# anodeBoard.net
KiCad netlist of a schematic drawn in EAGLE
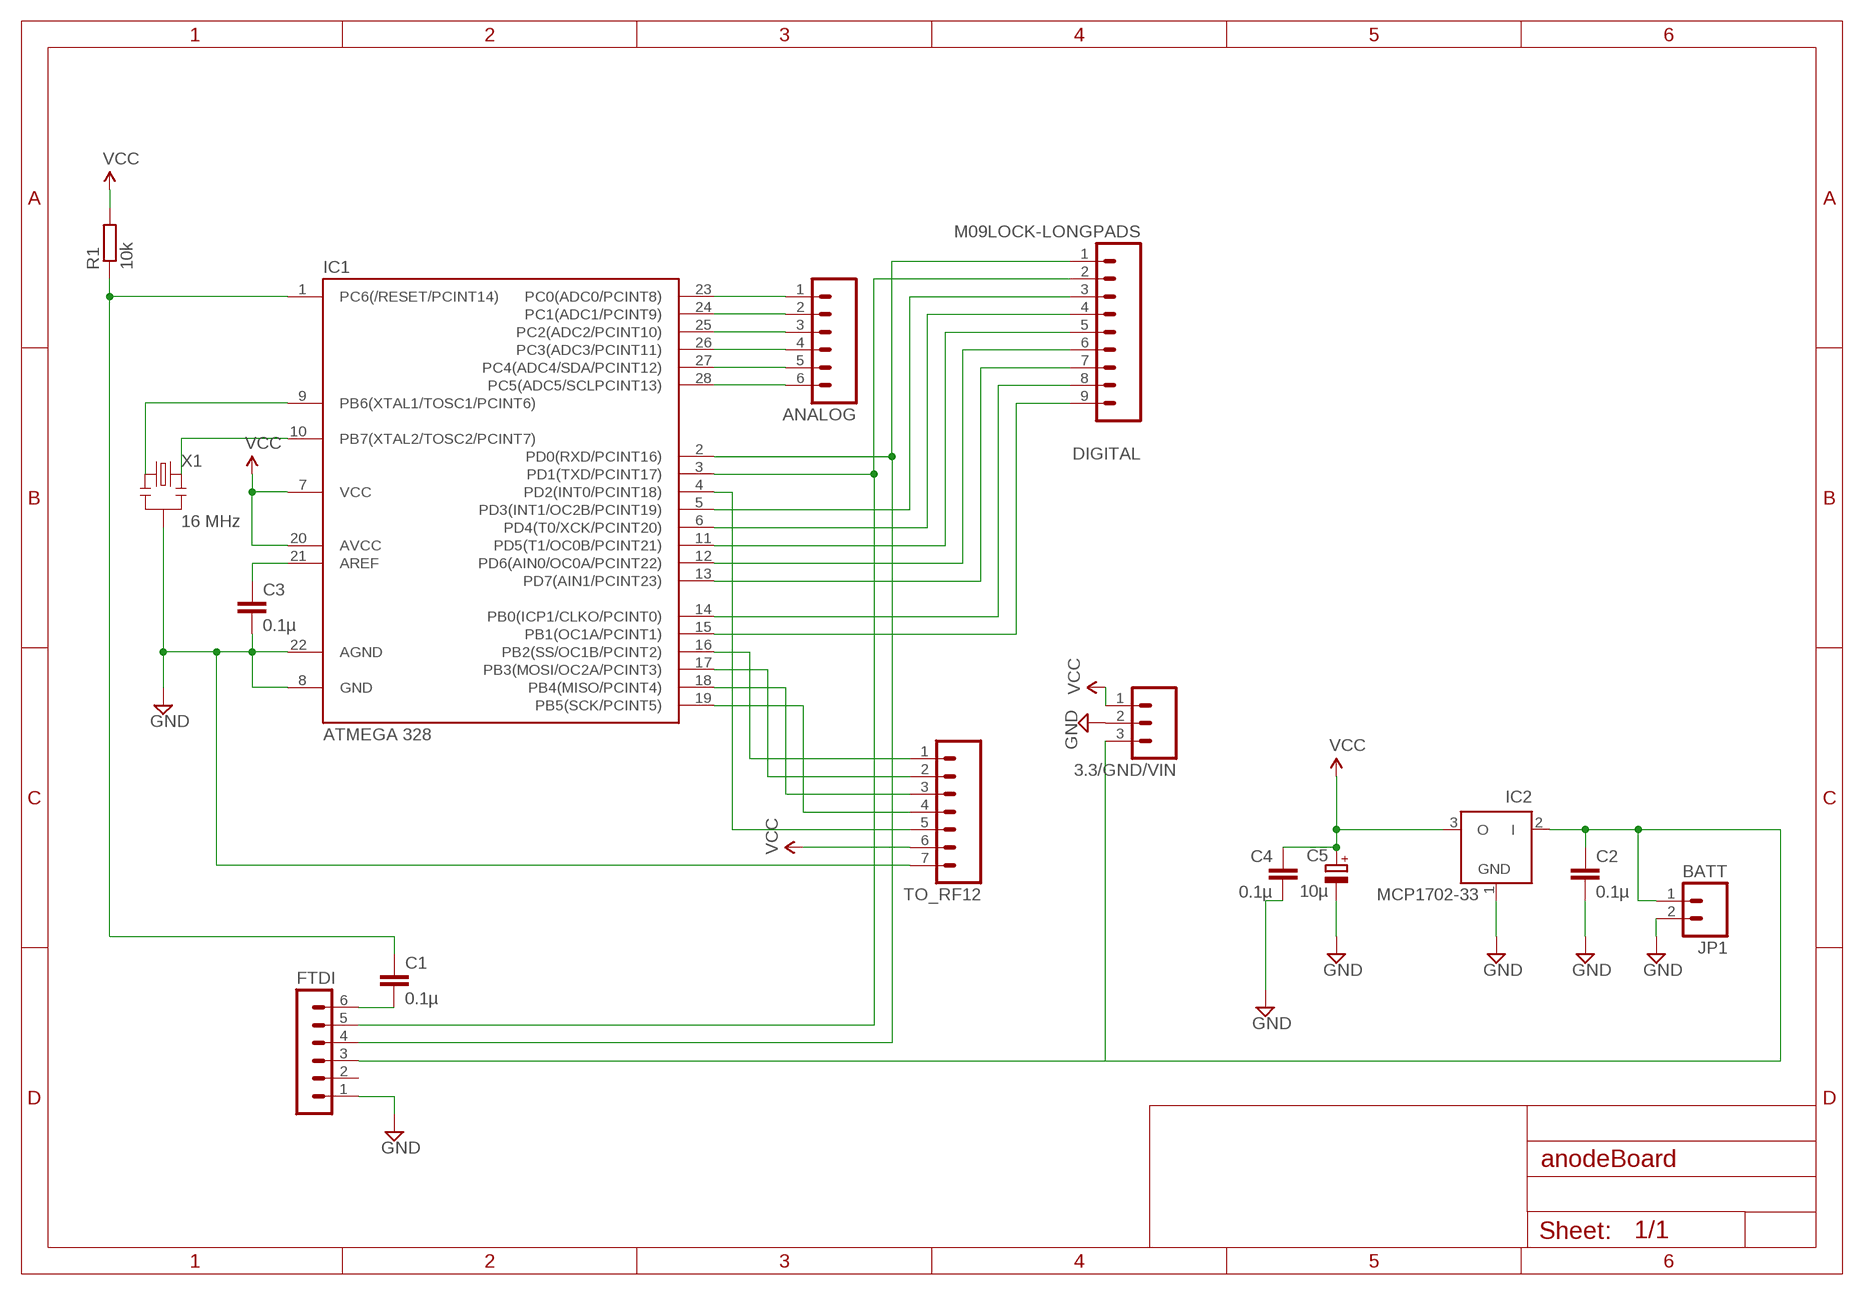
[diagram p0: schematic, sheet 1]

(export (version "E")
  (design (tool "Eeschema 10.0.6"))
  (components
    (comp (ref "3.3/GND/VIN")
      (value "M03LOCK_LONGPADS")
      (footprint "eagle-import:1X03_LOCK_LONGPADS")
      (libsource (lib "eagle-import") (part "M03LOCK_LONGPADS"))
    )
    (comp (ref "ANALOG")
      (value "M06LOCK_LONGPADS")
      (footprint "eagle-import:1X06_LOCK_LONGPADS")
      (libsource (lib "eagle-import") (part "M06LOCK_LONGPADS"))
    )
    (comp (ref "C1")
      (value "0.1µ")
      (footprint "eagle-import:C025-024X044")
      (libsource (lib "eagle-import") (part "C-EU025-024X044"))
    )
    (comp (ref "C2")
      (value "0.1µ")
      (footprint "eagle-import:C025-024X044")
      (libsource (lib "eagle-import") (part "C-EU025-024X044"))
    )
    (comp (ref "C3")
      (value "0.1µ")
      (footprint "eagle-import:C025-024X044")
      (libsource (lib "eagle-import") (part "C-EU025-024X044"))
    )
    (comp (ref "C4")
      (value "0.1µ")
      (footprint "eagle-import:C025-024X044")
      (libsource (lib "eagle-import") (part "C-EU025-024X044"))
    )
    (comp (ref "C5")
      (value "10µ")
      (footprint "eagle-import:E1,8-4")
      (libsource (lib "eagle-import") (part "CPOL-EUE1.8-4"))
    )
    (comp (ref "DIGITAL")
      (value "M09LOCK-LONGPADS")
      (footprint "eagle-import:1X09_LOCK_LONGPADS")
      (libsource (lib "eagle-import") (part "M09LOCK-LONGPADS"))
    )
    (comp (ref "FTDI")
      (value "FTDI")
      (footprint "eagle-import:MA06-1")
      (libsource (lib "eagle-import") (part "MA06-1"))
    )
    (comp (ref "IC1")
      (value "ATMEGA 328")
      (footprint "eagle-import:DIL28-3")
      (libsource (lib "eagle-import") (part "ATMEGA48/88/168-PU"))
    )
    (comp (ref "IC2")
      (value "MCP1702-33")
      (footprint "eagle-import:TO92")
      (libsource (lib "eagle-import") (part "MCP1702Z"))
    )
    (comp (ref "JP1")
      (value "BATT")
      (footprint "eagle-import:1X02_LOCK_LONGPADS")
      (libsource (lib "eagle-import") (part "M02LOCK_LONGPADS"))
    )
    (comp (ref "R1")
      (value "10k")
      (footprint "eagle-import:0204_7")
      (libsource (lib "eagle-import") (part "R-EU_0204/7"))
    )
    (comp (ref "TO_RF12")
      (value "M07LOCK_LONGPADS")
      (footprint "eagle-import:1X07_LOCK_LONGPADS")
      (libsource (lib "eagle-import") (part "M07LOCK_LONGPADS"))
    )
    (comp (ref "X1")
      (value "16 MHz")
      (footprint "eagle-import:RESONATOR-PTH")
      (libsource (lib "eagle-import") (part "RESONATORPTH"))
    )
  )
  (nets
    (net (code "1") (name "GND") (class "Default")
      (node (ref "3.3/GND/VIN") (pin "2") (pinfunction "2_2") (pintype "passive"))
      (node (ref "C2") (pin "2") (pinfunction "2_2") (pintype "passive"))
      (node (ref "C3") (pin "2") (pinfunction "2_2") (pintype "passive"))
      (node (ref "C4") (pin "2") (pinfunction "2_2") (pintype "passive"))
      (node (ref "C5") (pin "-") (pinfunction "-_-") (pintype "passive"))
      (node (ref "FTDI") (pin "1") (pinfunction "1_1") (pintype "passive"))
      (node (ref "IC1") (pin "22") (pinfunction "AGND_22") (pintype "power_in"))
      (node (ref "IC1") (pin "8") (pinfunction "GND_8") (pintype "power_in"))
      (node (ref "IC2") (pin "1") (pinfunction "GND_1") (pintype "power_in"))
      (node (ref "JP1") (pin "2") (pinfunction "2_2") (pintype "passive"))
      (node (ref "TO_RF12") (pin "7") (pinfunction "7_7") (pintype "passive"))
      (node (ref "X1") (pin "2") (pinfunction "2_2") (pintype "passive"))
    )
    (net (code "2") (name "Net-(C1-Pad2)") (class "Default")
      (node (ref "C1") (pin "2") (pinfunction "2_2") (pintype "passive"))
      (node (ref "FTDI") (pin "6") (pinfunction "6_6") (pintype "passive"))
    )
    (net (code "3") (name "Net-(IC1-AREF)") (class "Default")
      (node (ref "C3") (pin "1") (pinfunction "1_1") (pintype "passive"))
      (node (ref "IC1") (pin "21") (pinfunction "AREF_21") (pintype "passive"))
    )
    (net (code "4") (name "Net-(IC1-PB0(ICP1{slash}CLKO{slash}PCINT0))") (class "Default")
      (node (ref "DIGITAL") (pin "8") (pinfunction "8_8") (pintype "passive"))
      (node (ref "IC1") (pin "14") (pinfunction "PB0(ICP1/CLKO/PCINT0)_14") (pintype "bidirectional"))
    )
    (net (code "5") (name "Net-(IC1-PB1(OC1A{slash}PCINT1))") (class "Default")
      (node (ref "DIGITAL") (pin "9") (pinfunction "9_9") (pintype "passive"))
      (node (ref "IC1") (pin "15") (pinfunction "PB1(OC1A/PCINT1)_15") (pintype "bidirectional"))
    )
    (net (code "6") (name "Net-(IC1-PB2(SS{slash}OC1B{slash}PCINT2))") (class "Default")
      (node (ref "IC1") (pin "16") (pinfunction "PB2(SS/OC1B/PCINT2)_16") (pintype "bidirectional"))
      (node (ref "TO_RF12") (pin "1") (pinfunction "1_1") (pintype "passive"))
    )
    (net (code "7") (name "Net-(IC1-PB3(MOSI{slash}OC2A{slash}PCINT3))") (class "Default")
      (node (ref "IC1") (pin "17") (pinfunction "PB3(MOSI/OC2A/PCINT3)_17") (pintype "bidirectional"))
      (node (ref "TO_RF12") (pin "2") (pinfunction "2_2") (pintype "passive"))
    )
    (net (code "8") (name "Net-(IC1-PB4(MISO{slash}PCINT4))") (class "Default")
      (node (ref "IC1") (pin "18") (pinfunction "PB4(MISO/PCINT4)_18") (pintype "bidirectional"))
      (node (ref "TO_RF12") (pin "3") (pinfunction "3_3") (pintype "passive"))
    )
    (net (code "9") (name "Net-(IC1-PB5(SCK{slash}PCINT5))") (class "Default")
      (node (ref "IC1") (pin "19") (pinfunction "PB5(SCK/PCINT5)_19") (pintype "bidirectional"))
      (node (ref "TO_RF12") (pin "4") (pinfunction "4_4") (pintype "passive"))
    )
    (net (code "10") (name "Net-(IC1-PB6(XTAL1{slash}TOSC1{slash}PCINT6))") (class "Default")
      (node (ref "IC1") (pin "9") (pinfunction "PB6(XTAL1/TOSC1/PCINT6)_9") (pintype "bidirectional"))
      (node (ref "X1") (pin "1") (pinfunction "1_1") (pintype "passive"))
    )
    (net (code "11") (name "Net-(IC1-PB7(XTAL2{slash}TOSC2{slash}PCINT7))") (class "Default")
      (node (ref "IC1") (pin "10") (pinfunction "PB7(XTAL2/TOSC2/PCINT7)_10") (pintype "bidirectional"))
      (node (ref "X1") (pin "3") (pinfunction "3_3") (pintype "passive"))
    )
    (net (code "12") (name "Net-(IC1-PC0(ADC0{slash}PCINT8))") (class "Default")
      (node (ref "ANALOG") (pin "1") (pinfunction "1_1") (pintype "passive"))
      (node (ref "IC1") (pin "23") (pinfunction "PC0(ADC0/PCINT8)_23") (pintype "bidirectional"))
    )
    (net (code "13") (name "Net-(IC1-PC1(ADC1{slash}PCINT9))") (class "Default")
      (node (ref "ANALOG") (pin "2") (pinfunction "2_2") (pintype "passive"))
      (node (ref "IC1") (pin "24") (pinfunction "PC1(ADC1/PCINT9)_24") (pintype "bidirectional"))
    )
    (net (code "14") (name "Net-(IC1-PC2(ADC2{slash}PCINT10))") (class "Default")
      (node (ref "ANALOG") (pin "3") (pinfunction "3_3") (pintype "passive"))
      (node (ref "IC1") (pin "25") (pinfunction "PC2(ADC2/PCINT10)_25") (pintype "bidirectional"))
    )
    (net (code "15") (name "Net-(IC1-PC3(ADC3{slash}PCINT11))") (class "Default")
      (node (ref "ANALOG") (pin "4") (pinfunction "4_4") (pintype "passive"))
      (node (ref "IC1") (pin "26") (pinfunction "PC3(ADC3/PCINT11)_26") (pintype "bidirectional"))
    )
    (net (code "16") (name "Net-(IC1-PC4(ADC4{slash}SDA{slash}PCINT12))") (class "Default")
      (node (ref "ANALOG") (pin "5") (pinfunction "5_5") (pintype "passive"))
      (node (ref "IC1") (pin "27") (pinfunction "PC4(ADC4/SDA/PCINT12)_27") (pintype "bidirectional"))
    )
    (net (code "17") (name "Net-(IC1-PC5(ADC5{slash}SCLPCINT13))") (class "Default")
      (node (ref "ANALOG") (pin "6") (pinfunction "6_6") (pintype "passive"))
      (node (ref "IC1") (pin "28") (pinfunction "PC5(ADC5/SCLPCINT13)_28") (pintype "bidirectional"))
    )
    (net (code "18") (name "Net-(IC1-PC6({slash}RESET{slash}PCINT14))") (class "Default")
      (node (ref "C1") (pin "1") (pinfunction "1_1") (pintype "passive"))
      (node (ref "IC1") (pin "1") (pinfunction "PC6(/RESET/PCINT14)_1") (pintype "bidirectional"))
      (node (ref "R1") (pin "1") (pinfunction "1_1") (pintype "passive"))
    )
    (net (code "19") (name "Net-(IC1-PD0(RXD{slash}PCINT16))") (class "Default")
      (node (ref "DIGITAL") (pin "1") (pinfunction "1_1") (pintype "passive"))
      (node (ref "FTDI") (pin "4") (pinfunction "4_4") (pintype "passive"))
      (node (ref "IC1") (pin "2") (pinfunction "PD0(RXD/PCINT16)_2") (pintype "bidirectional"))
    )
    (net (code "20") (name "Net-(IC1-PD1(TXD{slash}PCINT17))") (class "Default")
      (node (ref "DIGITAL") (pin "2") (pinfunction "2_2") (pintype "passive"))
      (node (ref "FTDI") (pin "5") (pinfunction "5_5") (pintype "passive"))
      (node (ref "IC1") (pin "3") (pinfunction "PD1(TXD/PCINT17)_3") (pintype "bidirectional"))
    )
    (net (code "21") (name "Net-(IC1-PD2(INT0{slash}PCINT18))") (class "Default")
      (node (ref "IC1") (pin "4") (pinfunction "PD2(INT0/PCINT18)_4") (pintype "bidirectional"))
      (node (ref "TO_RF12") (pin "5") (pinfunction "5_5") (pintype "passive"))
    )
    (net (code "22") (name "Net-(IC1-PD3(INT1{slash}OC2B{slash}PCINT19))") (class "Default")
      (node (ref "DIGITAL") (pin "3") (pinfunction "3_3") (pintype "passive"))
      (node (ref "IC1") (pin "5") (pinfunction "PD3(INT1/OC2B/PCINT19)_5") (pintype "bidirectional"))
    )
    (net (code "23") (name "Net-(IC1-PD4(T0{slash}XCK{slash}PCINT20))") (class "Default")
      (node (ref "DIGITAL") (pin "4") (pinfunction "4_4") (pintype "passive"))
      (node (ref "IC1") (pin "6") (pinfunction "PD4(T0/XCK/PCINT20)_6") (pintype "bidirectional"))
    )
    (net (code "24") (name "Net-(IC1-PD5(T1{slash}OC0B{slash}PCINT21))") (class "Default")
      (node (ref "DIGITAL") (pin "5") (pinfunction "5_5") (pintype "passive"))
      (node (ref "IC1") (pin "11") (pinfunction "PD5(T1/OC0B/PCINT21)_11") (pintype "bidirectional"))
    )
    (net (code "25") (name "Net-(IC1-PD6(AIN0{slash}OC0A{slash}PCINT22))") (class "Default")
      (node (ref "DIGITAL") (pin "6") (pinfunction "6_6") (pintype "passive"))
      (node (ref "IC1") (pin "12") (pinfunction "PD6(AIN0/OC0A/PCINT22)_12") (pintype "bidirectional"))
    )
    (net (code "26") (name "Net-(IC1-PD7(AIN1{slash}PCINT23))") (class "Default")
      (node (ref "DIGITAL") (pin "7") (pinfunction "7_7") (pintype "passive"))
      (node (ref "IC1") (pin "13") (pinfunction "PD7(AIN1/PCINT23)_13") (pintype "bidirectional"))
    )
    (net (code "27") (name "Net-(IC2-I)") (class "Default")
      (node (ref "3.3/GND/VIN") (pin "3") (pinfunction "3_3") (pintype "passive"))
      (node (ref "C2") (pin "1") (pinfunction "1_1") (pintype "passive"))
      (node (ref "FTDI") (pin "3") (pinfunction "3_3") (pintype "passive"))
      (node (ref "IC2") (pin "2") (pinfunction "I_2") (pintype "input"))
      (node (ref "JP1") (pin "1") (pinfunction "1_1") (pintype "passive"))
    )
    (net (code "28") (name "VCC") (class "Default")
      (node (ref "3.3/GND/VIN") (pin "1") (pinfunction "1_1") (pintype "passive"))
      (node (ref "C4") (pin "1") (pinfunction "1_1") (pintype "passive"))
      (node (ref "C5") (pin "+") (pinfunction "+_+") (pintype "passive"))
      (node (ref "IC1") (pin "20") (pinfunction "AVCC_20") (pintype "passive"))
      (node (ref "IC1") (pin "7") (pinfunction "VCC_7") (pintype "power_in"))
      (node (ref "IC2") (pin "3") (pinfunction "O_3") (pintype "input"))
      (node (ref "R1") (pin "2") (pinfunction "2_2") (pintype "passive"))
      (node (ref "TO_RF12") (pin "6") (pinfunction "6_6") (pintype "passive"))
    )
    (net (code "29") (name "unconnected-(FTDI-Pad2)") (class "Default")
      (node (ref "FTDI") (pin "2") (pinfunction "2_2") (pintype "passive"))
    )
  )
)
